# mcu.net
KiCad netlist of a schematic drawn in Altium Designer
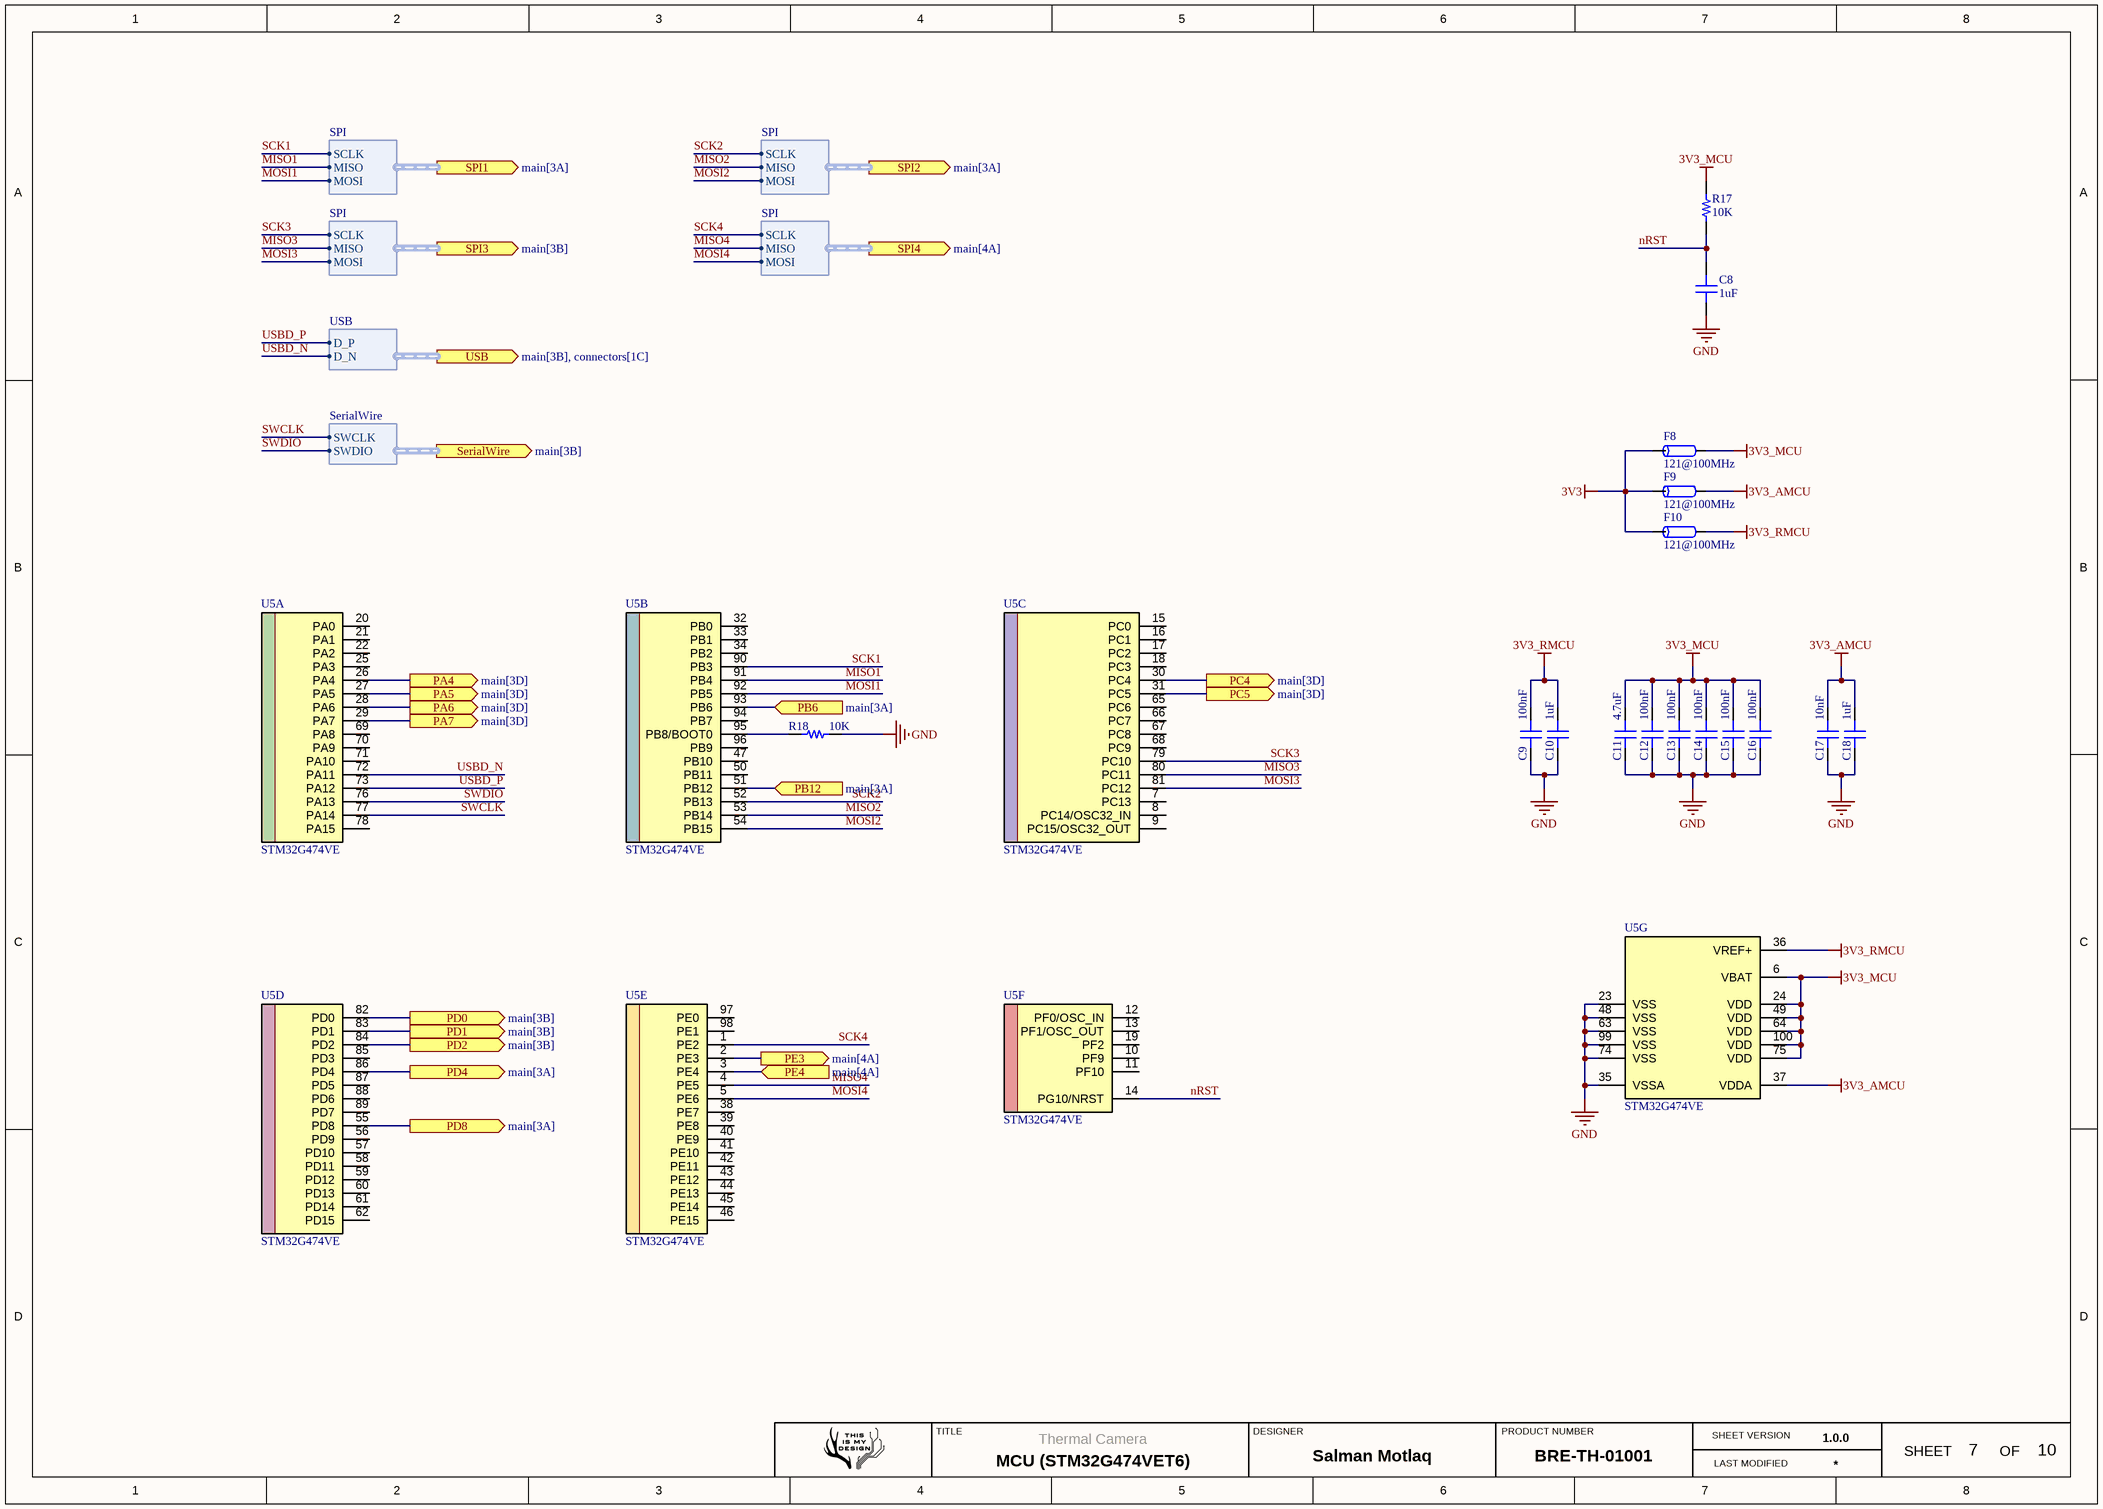
[diagram p0: mcu.SchDoc]

(export (version "E")
  (design (tool "Eeschema 10.0.6"))
  (components
    (comp (ref "C8")
      (value "1uF")
      (footprint "CAP 0603_1608")
      (description "SMT Capacitor")
      (libsource (lib "Capacitor") (part "Cap 0603"))
    )
    (comp (ref "C9")
      (value "100nF")
      (footprint "CAP 0603_1608")
      (description "SMT Capacitor")
      (libsource (lib "Capacitor") (part "Cap 0603"))
    )
    (comp (ref "C10")
      (value "1uF")
      (footprint "CAP 0603_1608")
      (description "SMT Capacitor")
      (libsource (lib "Capacitor") (part "Cap 0603"))
    )
    (comp (ref "C11")
      (value "4.7uF")
      (footprint "CAP 0805_2012")
      (description "SMT Capacitor")
      (libsource (lib "Capacitor") (part "Cap 0805"))
    )
    (comp (ref "C12")
      (value "100nF")
      (footprint "CAP 0603_1608")
      (description "SMT Capacitor")
      (libsource (lib "Capacitor") (part "Cap 0603"))
    )
    (comp (ref "C13")
      (value "100nF")
      (footprint "CAP 0603_1608")
      (description "SMT Capacitor")
      (libsource (lib "Capacitor") (part "Cap 0603"))
    )
    (comp (ref "C14")
      (value "100nF")
      (footprint "CAP 0603_1608")
      (description "SMT Capacitor")
      (libsource (lib "Capacitor") (part "Cap 0603"))
    )
    (comp (ref "C15")
      (value "100nF")
      (footprint "CAP 0603_1608")
      (description "SMT Capacitor")
      (libsource (lib "Capacitor") (part "Cap 0603"))
    )
    (comp (ref "C16")
      (value "100nF")
      (footprint "CAP 0603_1608")
      (description "SMT Capacitor")
      (libsource (lib "Capacitor") (part "Cap 0603"))
    )
    (comp (ref "C17")
      (value "10nF")
      (footprint "CAP 0603_1608")
      (description "SMT Capacitor")
      (libsource (lib "Capacitor") (part "Cap 0603"))
    )
    (comp (ref "C18")
      (value "1uF")
      (footprint "CAP 0603_1608")
      (description "SMT Capacitor")
      (libsource (lib "Capacitor") (part "Cap 0603"))
    )
    (comp (ref "F8")
      (value "121@100MHz")
      (footprint "Ferrite-0805")
      (description "Ferrite Bead")
      (libsource (lib "Salman_lib") (part "Ferrite Bead"))
    )
    (comp (ref "F9")
      (value "121@100MHz")
      (footprint "Ferrite-0805")
      (description "Ferrite Bead")
      (libsource (lib "Salman_lib") (part "Ferrite Bead"))
    )
    (comp (ref "F10")
      (value "121@100MHz")
      (footprint "Ferrite-0805")
      (description "Ferrite Bead")
      (libsource (lib "Salman_lib") (part "Ferrite Bead"))
    )
    (comp (ref "R17")
      (value "10K")
      (footprint "RES 0603_1608")
      (description "SMT Resistor")
      (libsource (lib "Resistor") (part "Res 0603"))
    )
    (comp (ref "R18")
      (value "10K")
      (footprint "RES 0402_1005")
      (description "SMT Resistor")
      (libsource (lib "Resistor") (part "Res 0402"))
    )
    (comp (ref "U5")
      (value "STM32G474VE")
      (footprint "LQFP100")
      (libsource (lib "Salman_lib") (part "STM32G474VE"))
    )
  )
  (nets
    (net (code "4") (name "/MISO1") (class "Default")
      (node (ref "U5") (pin "91") (pinfunction "PB4_91") (pintype "passive"))
    )
    (net (code "5") (name "/MISO2") (class "Default")
      (node (ref "U5") (pin "53") (pinfunction "PB14_53") (pintype "passive"))
    )
    (net (code "6") (name "/MISO3") (class "Default")
      (node (ref "U5") (pin "80") (pinfunction "PC11_80") (pintype "passive"))
    )
    (net (code "7") (name "/MISO4") (class "Default")
      (node (ref "U5") (pin "4") (pinfunction "PE5_4") (pintype "passive"))
    )
    (net (code "8") (name "/MOSI1") (class "Default")
      (node (ref "U5") (pin "92") (pinfunction "PB5_92") (pintype "passive"))
    )
    (net (code "9") (name "/MOSI2") (class "Default")
      (node (ref "U5") (pin "54") (pinfunction "PB15_54") (pintype "passive"))
    )
    (net (code "10") (name "/MOSI3") (class "Default")
      (node (ref "U5") (pin "81") (pinfunction "PC12_81") (pintype "passive"))
    )
    (net (code "11") (name "/MOSI4") (class "Default")
      (node (ref "U5") (pin "5") (pinfunction "PE6_5") (pintype "passive"))
    )
    (net (code "12") (name "/PA4") (class "Default")
      (node (ref "U5") (pin "26") (pinfunction "PA4_26") (pintype "passive"))
    )
    (net (code "13") (name "/PA5") (class "Default")
      (node (ref "U5") (pin "27") (pinfunction "PA5_27") (pintype "passive"))
    )
    (net (code "14") (name "/PA6") (class "Default")
      (node (ref "U5") (pin "28") (pinfunction "PA6_28") (pintype "passive"))
    )
    (net (code "15") (name "/PA7") (class "Default")
      (node (ref "U5") (pin "29") (pinfunction "PA7_29") (pintype "passive"))
    )
    (net (code "16") (name "/PB6") (class "Default")
      (node (ref "U5") (pin "93") (pinfunction "PB6_93") (pintype "passive"))
    )
    (net (code "17") (name "/PB12") (class "Default")
      (node (ref "U5") (pin "51") (pinfunction "PB12_51") (pintype "passive"))
    )
    (net (code "18") (name "/PC4") (class "Default")
      (node (ref "U5") (pin "30") (pinfunction "PC4_30") (pintype "passive"))
    )
    (net (code "19") (name "/PC5") (class "Default")
      (node (ref "U5") (pin "31") (pinfunction "PC5_31") (pintype "passive"))
    )
    (net (code "20") (name "/PD0") (class "Default")
      (node (ref "U5") (pin "82") (pinfunction "PD0_82") (pintype "passive"))
    )
    (net (code "21") (name "/PD1") (class "Default")
      (node (ref "U5") (pin "83") (pinfunction "PD1_83") (pintype "passive"))
    )
    (net (code "22") (name "/PD2") (class "Default")
      (node (ref "U5") (pin "84") (pinfunction "PD2_84") (pintype "passive"))
    )
    (net (code "23") (name "/PD4") (class "Default")
      (node (ref "U5") (pin "86") (pinfunction "PD4_86") (pintype "passive"))
    )
    (net (code "24") (name "/PD8") (class "Default")
      (node (ref "U5") (pin "55") (pinfunction "PD8_55") (pintype "passive"))
    )
    (net (code "25") (name "/PE3") (class "Default")
      (node (ref "U5") (pin "2") (pinfunction "PE3_2") (pintype "passive"))
    )
    (net (code "26") (name "/PE4") (class "Default")
      (node (ref "U5") (pin "3") (pinfunction "PE4_3") (pintype "passive"))
    )
    (net (code "27") (name "/SCK1") (class "Default")
      (node (ref "U5") (pin "90") (pinfunction "PB3_90") (pintype "passive"))
    )
    (net (code "28") (name "/SCK2") (class "Default")
      (node (ref "U5") (pin "52") (pinfunction "PB13_52") (pintype "passive"))
    )
    (net (code "29") (name "/SCK3") (class "Default")
      (node (ref "U5") (pin "79") (pinfunction "PC10_79") (pintype "passive"))
    )
    (net (code "30") (name "/SCK4") (class "Default")
      (node (ref "U5") (pin "1") (pinfunction "PE2_1") (pintype "passive"))
    )
    (net (code "31") (name "/SWCLK") (class "Default")
      (node (ref "U5") (pin "77") (pinfunction "PA14_77") (pintype "passive"))
    )
    (net (code "32") (name "/SWDIO") (class "Default")
      (node (ref "U5") (pin "76") (pinfunction "PA13_76") (pintype "passive"))
    )
    (net (code "33") (name "/USBD_N") (class "Default")
      (node (ref "U5") (pin "72") (pinfunction "PA11_72") (pintype "passive"))
    )
    (net (code "34") (name "/USBD_P") (class "Default")
      (node (ref "U5") (pin "73") (pinfunction "PA12_73") (pintype "passive"))
    )
    (net (code "35") (name "/nRST") (class "Default")
      (node (ref "C8") (pin "2") (pinfunction "2_2") (pintype "passive"))
      (node (ref "R17") (pin "1") (pinfunction "1_1") (pintype "passive"))
      (node (ref "U5") (pin "14") (pinfunction "PG10/NRST_14") (pintype "passive"))
    )
    (net (code "39") (name "3V3") (class "Default")
      (node (ref "F10") (pin "2") (pinfunction "66_2") (pintype "passive"))
      (node (ref "F8") (pin "2") (pinfunction "66_2") (pintype "passive"))
      (node (ref "F9") (pin "2") (pinfunction "66_2") (pintype "passive"))
    )
    (net (code "40") (name "3V3_AMCU") (class "Default")
      (node (ref "C17") (pin "2") (pinfunction "2_2") (pintype "passive"))
      (node (ref "C18") (pin "2") (pinfunction "2_2") (pintype "passive"))
      (node (ref "F9") (pin "1") (pinfunction "67_1") (pintype "passive"))
      (node (ref "U5") (pin "37") (pinfunction "VDDA_37") (pintype "passive"))
    )
    (net (code "41") (name "3V3_MCU") (class "Default")
      (node (ref "C11") (pin "2") (pinfunction "2_2") (pintype "passive"))
      (node (ref "C12") (pin "2") (pinfunction "2_2") (pintype "passive"))
      (node (ref "C13") (pin "2") (pinfunction "2_2") (pintype "passive"))
      (node (ref "C14") (pin "2") (pinfunction "2_2") (pintype "passive"))
      (node (ref "C15") (pin "2") (pinfunction "2_2") (pintype "passive"))
      (node (ref "C16") (pin "2") (pinfunction "2_2") (pintype "passive"))
      (node (ref "F8") (pin "1") (pinfunction "67_1") (pintype "passive"))
      (node (ref "R17") (pin "2") (pinfunction "2_2") (pintype "passive"))
      (node (ref "U5") (pin "100") (pinfunction "VDD_100") (pintype "passive"))
      (node (ref "U5") (pin "24") (pinfunction "VDD_24") (pintype "passive"))
      (node (ref "U5") (pin "49") (pinfunction "VDD_49") (pintype "passive"))
      (node (ref "U5") (pin "6") (pinfunction "VBAT_6") (pintype "passive"))
      (node (ref "U5") (pin "64") (pinfunction "VDD_64") (pintype "passive"))
      (node (ref "U5") (pin "75") (pinfunction "VDD_75") (pintype "passive"))
    )
    (net (code "42") (name "3V3_RMCU") (class "Default")
      (node (ref "C10") (pin "2") (pinfunction "2_2") (pintype "passive"))
      (node (ref "C9") (pin "2") (pinfunction "2_2") (pintype "passive"))
      (node (ref "F10") (pin "1") (pinfunction "67_1") (pintype "passive"))
      (node (ref "U5") (pin "36") (pinfunction "VREF+_36") (pintype "passive"))
    )
    (net (code "43") (name "GND") (class "Default")
      (node (ref "C10") (pin "1") (pinfunction "1_1") (pintype "passive"))
      (node (ref "C11") (pin "1") (pinfunction "1_1") (pintype "passive"))
      (node (ref "C12") (pin "1") (pinfunction "1_1") (pintype "passive"))
      (node (ref "C13") (pin "1") (pinfunction "1_1") (pintype "passive"))
      (node (ref "C14") (pin "1") (pinfunction "1_1") (pintype "passive"))
      (node (ref "C15") (pin "1") (pinfunction "1_1") (pintype "passive"))
      (node (ref "C16") (pin "1") (pinfunction "1_1") (pintype "passive"))
      (node (ref "C17") (pin "1") (pinfunction "1_1") (pintype "passive"))
      (node (ref "C18") (pin "1") (pinfunction "1_1") (pintype "passive"))
      (node (ref "C8") (pin "1") (pinfunction "1_1") (pintype "passive"))
      (node (ref "C9") (pin "1") (pinfunction "1_1") (pintype "passive"))
      (node (ref "R18") (pin "2") (pinfunction "2_2") (pintype "passive"))
      (node (ref "U5") (pin "23") (pinfunction "VSS_23") (pintype "passive"))
      (node (ref "U5") (pin "35") (pinfunction "VSSA_35") (pintype "passive"))
      (node (ref "U5") (pin "48") (pinfunction "VSS_48") (pintype "passive"))
      (node (ref "U5") (pin "63") (pinfunction "VSS_63") (pintype "passive"))
      (node (ref "U5") (pin "74") (pinfunction "VSS_74") (pintype "passive"))
      (node (ref "U5") (pin "99") (pinfunction "VSS_99") (pintype "passive"))
    )
    (net (code "44") (name "Net-(U5B-PB8{slash}BOOT0)") (class "Default")
      (node (ref "R18") (pin "1") (pinfunction "1_1") (pintype "passive"))
      (node (ref "U5") (pin "95") (pinfunction "PB8/BOOT0_95") (pintype "passive"))
    )
    (net (code "45") (name "unconnected-(U5A-PA0-Pad20)") (class "Default")
      (node (ref "U5") (pin "20") (pinfunction "PA0_20") (pintype "passive"))
    )
    (net (code "46") (name "unconnected-(U5A-PA1-Pad21)") (class "Default")
      (node (ref "U5") (pin "21") (pinfunction "PA1_21") (pintype "passive"))
    )
    (net (code "47") (name "unconnected-(U5A-PA2-Pad22)") (class "Default")
      (node (ref "U5") (pin "22") (pinfunction "PA2_22") (pintype "passive"))
    )
    (net (code "48") (name "unconnected-(U5A-PA3-Pad25)") (class "Default")
      (node (ref "U5") (pin "25") (pinfunction "PA3_25") (pintype "passive"))
    )
    (net (code "49") (name "unconnected-(U5A-PA8-Pad69)") (class "Default")
      (node (ref "U5") (pin "69") (pinfunction "PA8_69") (pintype "passive"))
    )
    (net (code "50") (name "unconnected-(U5A-PA9-Pad70)") (class "Default")
      (node (ref "U5") (pin "70") (pinfunction "PA9_70") (pintype "passive"))
    )
    (net (code "51") (name "unconnected-(U5A-PA10-Pad71)") (class "Default")
      (node (ref "U5") (pin "71") (pinfunction "PA10_71") (pintype "passive"))
    )
    (net (code "52") (name "unconnected-(U5A-PA15-Pad78)") (class "Default")
      (node (ref "U5") (pin "78") (pinfunction "PA15_78") (pintype "passive"))
    )
    (net (code "53") (name "unconnected-(U5B-PB0-Pad32)") (class "Default")
      (node (ref "U5") (pin "32") (pinfunction "PB0_32") (pintype "passive"))
    )
    (net (code "54") (name "unconnected-(U5B-PB1-Pad33)") (class "Default")
      (node (ref "U5") (pin "33") (pinfunction "PB1_33") (pintype "passive"))
    )
    (net (code "55") (name "unconnected-(U5B-PB2-Pad34)") (class "Default")
      (node (ref "U5") (pin "34") (pinfunction "PB2_34") (pintype "passive"))
    )
    (net (code "56") (name "unconnected-(U5B-PB7-Pad94)") (class "Default")
      (node (ref "U5") (pin "94") (pinfunction "PB7_94") (pintype "passive"))
    )
    (net (code "57") (name "unconnected-(U5B-PB9-Pad96)") (class "Default")
      (node (ref "U5") (pin "96") (pinfunction "PB9_96") (pintype "passive"))
    )
    (net (code "58") (name "unconnected-(U5B-PB10-Pad47)") (class "Default")
      (node (ref "U5") (pin "47") (pinfunction "PB10_47") (pintype "passive"))
    )
    (net (code "59") (name "unconnected-(U5B-PB11-Pad50)") (class "Default")
      (node (ref "U5") (pin "50") (pinfunction "PB11_50") (pintype "passive"))
    )
    (net (code "60") (name "unconnected-(U5C-PC0-Pad15)") (class "Default")
      (node (ref "U5") (pin "15") (pinfunction "PC0_15") (pintype "passive"))
    )
    (net (code "61") (name "unconnected-(U5C-PC1-Pad16)") (class "Default")
      (node (ref "U5") (pin "16") (pinfunction "PC1_16") (pintype "passive"))
    )
    (net (code "62") (name "unconnected-(U5C-PC2-Pad17)") (class "Default")
      (node (ref "U5") (pin "17") (pinfunction "PC2_17") (pintype "passive"))
    )
    (net (code "63") (name "unconnected-(U5C-PC3-Pad18)") (class "Default")
      (node (ref "U5") (pin "18") (pinfunction "PC3_18") (pintype "passive"))
    )
    (net (code "64") (name "unconnected-(U5C-PC6-Pad65)") (class "Default")
      (node (ref "U5") (pin "65") (pinfunction "PC6_65") (pintype "passive"))
    )
    (net (code "65") (name "unconnected-(U5C-PC7-Pad66)") (class "Default")
      (node (ref "U5") (pin "66") (pinfunction "PC7_66") (pintype "passive"))
    )
    (net (code "66") (name "unconnected-(U5C-PC8-Pad67)") (class "Default")
      (node (ref "U5") (pin "67") (pinfunction "PC8_67") (pintype "passive"))
    )
    (net (code "67") (name "unconnected-(U5C-PC9-Pad68)") (class "Default")
      (node (ref "U5") (pin "68") (pinfunction "PC9_68") (pintype "passive"))
    )
    (net (code "68") (name "unconnected-(U5C-PC13-Pad7)") (class "Default")
      (node (ref "U5") (pin "7") (pinfunction "PC13_7") (pintype "passive"))
    )
    (net (code "69") (name "unconnected-(U5C-PC14{slash}OSC32_IN-Pad8)") (class "Default")
      (node (ref "U5") (pin "8") (pinfunction "PC14/OSC32_IN_8") (pintype "passive"))
    )
    (net (code "70") (name "unconnected-(U5C-PC15{slash}OSC32_OUT-Pad9)") (class "Default")
      (node (ref "U5") (pin "9") (pinfunction "PC15/OSC32_OUT_9") (pintype "passive"))
    )
    (net (code "71") (name "unconnected-(U5D-PD3-Pad85)") (class "Default")
      (node (ref "U5") (pin "85") (pinfunction "PD3_85") (pintype "passive"))
    )
    (net (code "72") (name "unconnected-(U5D-PD5-Pad87)") (class "Default")
      (node (ref "U5") (pin "87") (pinfunction "PD5_87") (pintype "passive"))
    )
    (net (code "73") (name "unconnected-(U5D-PD6-Pad88)") (class "Default")
      (node (ref "U5") (pin "88") (pinfunction "PD6_88") (pintype "passive"))
    )
    (net (code "74") (name "unconnected-(U5D-PD7-Pad89)") (class "Default")
      (node (ref "U5") (pin "89") (pinfunction "PD7_89") (pintype "passive"))
    )
    (net (code "75") (name "unconnected-(U5D-PD9-Pad56)") (class "Default")
      (node (ref "U5") (pin "56") (pinfunction "PD9_56") (pintype "passive"))
    )
    (net (code "76") (name "unconnected-(U5D-PD10-Pad57)") (class "Default")
      (node (ref "U5") (pin "57") (pinfunction "PD10_57") (pintype "passive"))
    )
    (net (code "77") (name "unconnected-(U5D-PD11-Pad58)") (class "Default")
      (node (ref "U5") (pin "58") (pinfunction "PD11_58") (pintype "passive"))
    )
    (net (code "78") (name "unconnected-(U5D-PD12-Pad59)") (class "Default")
      (node (ref "U5") (pin "59") (pinfunction "PD12_59") (pintype "passive"))
    )
    (net (code "79") (name "unconnected-(U5D-PD13-Pad60)") (class "Default")
      (node (ref "U5") (pin "60") (pinfunction "PD13_60") (pintype "passive"))
    )
    (net (code "80") (name "unconnected-(U5D-PD14-Pad61)") (class "Default")
      (node (ref "U5") (pin "61") (pinfunction "PD14_61") (pintype "passive"))
    )
    (net (code "81") (name "unconnected-(U5D-PD15-Pad62)") (class "Default")
      (node (ref "U5") (pin "62") (pinfunction "PD15_62") (pintype "passive"))
    )
    (net (code "82") (name "unconnected-(U5E-PE0-Pad97)") (class "Default")
      (node (ref "U5") (pin "97") (pinfunction "PE0_97") (pintype "passive"))
    )
    (net (code "83") (name "unconnected-(U5E-PE1-Pad98)") (class "Default")
      (node (ref "U5") (pin "98") (pinfunction "PE1_98") (pintype "passive"))
    )
    (net (code "84") (name "unconnected-(U5E-PE7-Pad38)") (class "Default")
      (node (ref "U5") (pin "38") (pinfunction "PE7_38") (pintype "passive"))
    )
    (net (code "85") (name "unconnected-(U5E-PE8-Pad39)") (class "Default")
      (node (ref "U5") (pin "39") (pinfunction "PE8_39") (pintype "passive"))
    )
    (net (code "86") (name "unconnected-(U5E-PE9-Pad40)") (class "Default")
      (node (ref "U5") (pin "40") (pinfunction "PE9_40") (pintype "passive"))
    )
    (net (code "87") (name "unconnected-(U5E-PE10-Pad41)") (class "Default")
      (node (ref "U5") (pin "41") (pinfunction "PE10_41") (pintype "passive"))
    )
    (net (code "88") (name "unconnected-(U5E-PE11-Pad42)") (class "Default")
      (node (ref "U5") (pin "42") (pinfunction "PE11_42") (pintype "passive"))
    )
    (net (code "89") (name "unconnected-(U5E-PE12-Pad43)") (class "Default")
      (node (ref "U5") (pin "43") (pinfunction "PE12_43") (pintype "passive"))
    )
    (net (code "90") (name "unconnected-(U5E-PE13-Pad44)") (class "Default")
      (node (ref "U5") (pin "44") (pinfunction "PE13_44") (pintype "passive"))
    )
    (net (code "91") (name "unconnected-(U5E-PE14-Pad45)") (class "Default")
      (node (ref "U5") (pin "45") (pinfunction "PE14_45") (pintype "passive"))
    )
    (net (code "92") (name "unconnected-(U5E-PE15-Pad46)") (class "Default")
      (node (ref "U5") (pin "46") (pinfunction "PE15_46") (pintype "passive"))
    )
    (net (code "93") (name "unconnected-(U5F-PF0{slash}OSC_IN-Pad12)") (class "Default")
      (node (ref "U5") (pin "12") (pinfunction "PF0/OSC_IN_12") (pintype "passive"))
    )
    (net (code "94") (name "unconnected-(U5F-PF1{slash}OSC_OUT-Pad13)") (class "Default")
      (node (ref "U5") (pin "13") (pinfunction "PF1/OSC_OUT_13") (pintype "passive"))
    )
    (net (code "95") (name "unconnected-(U5F-PF2-Pad19)") (class "Default")
      (node (ref "U5") (pin "19") (pinfunction "PF2_19") (pintype "passive"))
    )
    (net (code "96") (name "unconnected-(U5F-PF9-Pad10)") (class "Default")
      (node (ref "U5") (pin "10") (pinfunction "PF9_10") (pintype "passive"))
    )
    (net (code "97") (name "unconnected-(U5F-PF10-Pad11)") (class "Default")
      (node (ref "U5") (pin "11") (pinfunction "PF10_11") (pintype "passive"))
    )
  )
)
